# AI_SPEAKER.net
KiCad netlist of a schematic drawn in EAGLE
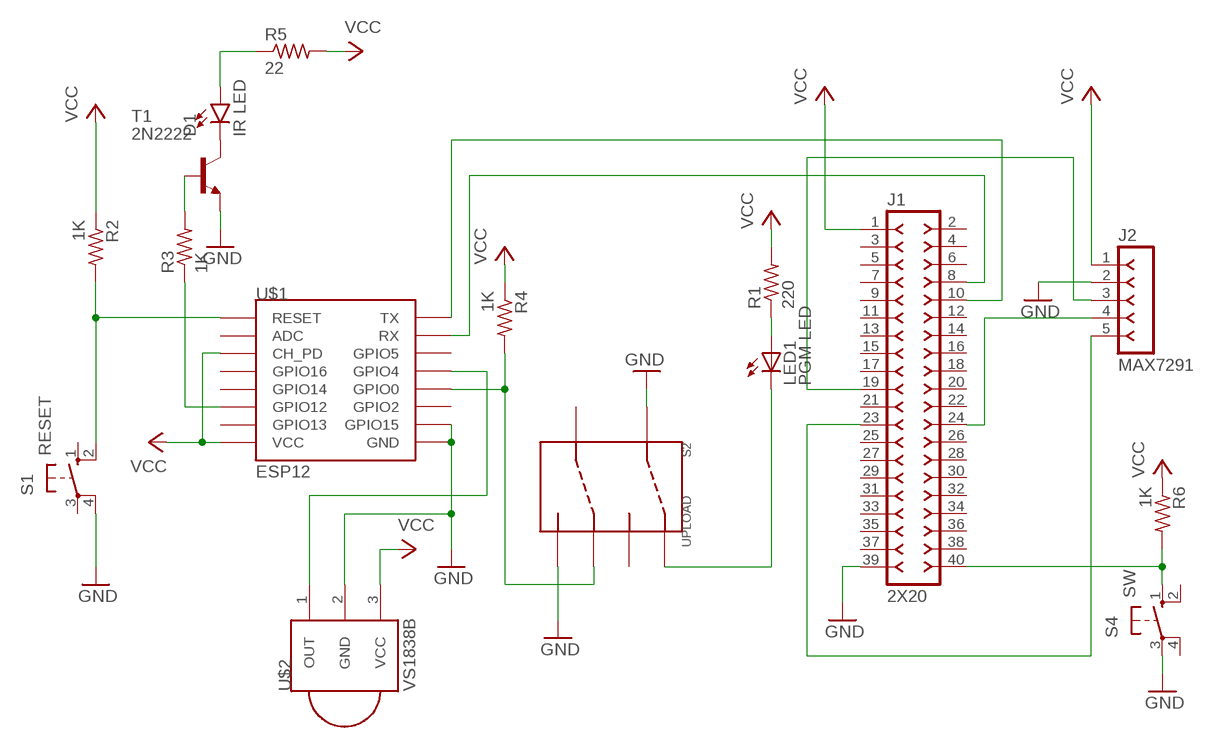
[diagram p0: schematic, sheet 1]

(export (version "E")
  (design (tool "Eeschema 10.0.6"))
  (components
    (comp (ref "D1")
      (value "IR LED")
      (footprint "eagle-import:LED_5MM")
      (fields (field (name "SPICEPREFIX") "D"))
      (libsource (lib "eagle-import") (part "LED-IRTSAL6100"))
    )
    (comp (ref "J1")
      (value "2X20")
      (footprint "eagle-import:DIL-100-2X20")
      (libsource (lib "eagle-import") (part "F-2X20-DIL-100"))
    )
    (comp (ref "J2")
      (value "MAX7291")
      (footprint "eagle-import:SIP-100-05-40")
      (libsource (lib "eagle-import") (part "F-1X05-SIP-100-40"))
    )
    (comp (ref "LED1")
      (value "PGM LED")
      (footprint "eagle-import:LED3MM")
      (libsource (lib "eagle-import") (part "LED3MM"))
    )
    (comp (ref "R1")
      (value "220")
      (footprint "eagle-import:0207_10")
      (libsource (lib "eagle-import") (part "R-US_0207/10"))
    )
    (comp (ref "R2")
      (value "1K")
      (footprint "eagle-import:0207_10")
      (libsource (lib "eagle-import") (part "R-US_0207/10"))
    )
    (comp (ref "R3")
      (value "1K")
      (footprint "eagle-import:0207_10")
      (libsource (lib "eagle-import") (part "R-US_0207/10"))
    )
    (comp (ref "R4")
      (value "1K")
      (footprint "eagle-import:0207_10")
      (libsource (lib "eagle-import") (part "R-US_0207/10"))
    )
    (comp (ref "R5")
      (value "22")
      (footprint "eagle-import:0207_10")
      (libsource (lib "eagle-import") (part "R-US_0207/10"))
    )
    (comp (ref "R6")
      (value "1K")
      (footprint "eagle-import:0207_10")
      (libsource (lib "eagle-import") (part "R-US_0207/10"))
    )
    (comp (ref "S1")
      (value "RESET")
      (footprint "eagle-import:B3F-10XX")
      (fields (field (name "MPN") "B3F-1000"))
      (libsource (lib "eagle-import") (part "10-XX"))
    )
    (comp (ref "S2")
      (value "UPLOAD")
      (footprint "eagle-import:SWITCH-6PIN-LOCK-2.54MM")
      (libsource (lib "eagle-import") (part "SWITCH-6PIN-LOCK-2.54MM"))
    )
    (comp (ref "S4")
      (value "SW")
      (footprint "eagle-import:B3F-10XX")
      (fields (field (name "MPN") "B3F-1000"))
      (libsource (lib "eagle-import") (part "10-XX"))
    )
    (comp (ref "T1")
      (value "2N2222")
      (footprint "eagle-import:TO92-EBC")
      (libsource (lib "eagle-import") (part "-NPN-TO92-EBC2N2222"))
    )
    (comp (ref "U$1")
      (value "ESP12")
      (footprint "eagle-import:ESP12")
      (libsource (lib "eagle-import") (part "ESP12"))
    )
    (comp (ref "U$2")
      (value "VS1838B")
      (footprint "eagle-import:PNA460XM")
      (libsource (lib "eagle-import") (part "PNA460XM"))
    )
  )
  (nets
    (net (code "1") (name "GND") (class "Default")
      (node (ref "J1") (pin "39") (pinfunction "39_39") (pintype "passive"))
      (node (ref "J2") (pin "2") (pinfunction "2_2") (pintype "passive"))
      (node (ref "S1") (pin "4") (pinfunction "P1_4") (pintype "passive"))
      (node (ref "S2") (pin "P$1") (pinfunction "P$1_P$1") (pintype "bidirectional"))
      (node (ref "S2") (pin "P$6") (pinfunction "P$6_P$6") (pintype "bidirectional"))
      (node (ref "S4") (pin "3") (pinfunction "P_3") (pintype "passive"))
      (node (ref "T1") (pin "E") (pinfunction "E_E") (pintype "passive"))
      (node (ref "U$1") (pin "GND") (pinfunction "GND_GND") (pintype "bidirectional"))
      (node (ref "U$1") (pin "GPIO15") (pinfunction "GPIO15_GPIO15") (pintype "bidirectional"))
      (node (ref "U$2") (pin "2") (pinfunction "GND_2") (pintype "power_in"))
    )
    (net (code "2") (name "Net-(D1-C)") (class "Default")
      (node (ref "D1") (pin "K") (pinfunction "C_K") (pintype "passive"))
      (node (ref "T1") (pin "C") (pinfunction "C_C") (pintype "passive"))
    )
    (net (code "3") (name "Net-(D1-PadA)") (class "Default")
      (node (ref "D1") (pin "A") (pinfunction "A_A") (pintype "passive"))
      (node (ref "R5") (pin "1") (pinfunction "1_1") (pintype "passive"))
    )
    (net (code "4") (name "Net-(J1-Pad8)") (class "Default")
      (node (ref "J1") (pin "8") (pinfunction "8_8") (pintype "passive"))
      (node (ref "U$1") (pin "RX") (pinfunction "RX_RX") (pintype "bidirectional"))
    )
    (net (code "5") (name "Net-(J1-Pad10)") (class "Default")
      (node (ref "J1") (pin "10") (pinfunction "10_10") (pintype "passive"))
      (node (ref "U$1") (pin "TX") (pinfunction "TX_TX") (pintype "bidirectional"))
    )
    (net (code "6") (name "Net-(J1-Pad19)") (class "Default")
      (node (ref "J1") (pin "19") (pinfunction "19_19") (pintype "passive"))
      (node (ref "J2") (pin "3") (pinfunction "3_3") (pintype "passive"))
    )
    (net (code "7") (name "Net-(J1-Pad23)") (class "Default")
      (node (ref "J1") (pin "23") (pinfunction "23_23") (pintype "passive"))
      (node (ref "J2") (pin "5") (pinfunction "5_5") (pintype "passive"))
    )
    (net (code "8") (name "Net-(J1-Pad24)") (class "Default")
      (node (ref "J1") (pin "24") (pinfunction "24_24") (pintype "passive"))
      (node (ref "J2") (pin "4") (pinfunction "4_4") (pintype "passive"))
    )
    (net (code "9") (name "Net-(LED1-C)") (class "Default")
      (node (ref "LED1") (pin "K") (pinfunction "C_K") (pintype "passive"))
      (node (ref "S2") (pin "P$2") (pinfunction "P$2_P$2") (pintype "bidirectional"))
    )
    (net (code "10") (name "Net-(LED1-PadA)") (class "Default")
      (node (ref "LED1") (pin "A") (pinfunction "A_A") (pintype "passive"))
      (node (ref "R1") (pin "1") (pinfunction "1_1") (pintype "passive"))
    )
    (net (code "11") (name "Net-(R3-Pad1)") (class "Default")
      (node (ref "R3") (pin "1") (pinfunction "1_1") (pintype "passive"))
      (node (ref "U$1") (pin "GPIO12") (pinfunction "GPIO12_GPIO12") (pintype "bidirectional"))
    )
    (net (code "12") (name "Net-(R3-Pad2)") (class "Default")
      (node (ref "R3") (pin "2") (pinfunction "2_2") (pintype "passive"))
      (node (ref "T1") (pin "B") (pinfunction "B_B") (pintype "passive"))
    )
    (net (code "13") (name "Net-(R4-Pad2)") (class "Default")
      (node (ref "R4") (pin "2") (pinfunction "2_2") (pintype "passive"))
      (node (ref "S2") (pin "P$5") (pinfunction "P$5_P$5") (pintype "bidirectional"))
      (node (ref "U$1") (pin "GPIO0") (pinfunction "GPIO0_GPIO0") (pintype "bidirectional"))
    )
    (net (code "14") (name "Net-(S1-S1)") (class "Default")
      (node (ref "R2") (pin "2") (pinfunction "2_2") (pintype "passive"))
      (node (ref "S1") (pin "2") (pinfunction "S1_2") (pintype "passive"))
      (node (ref "U$1") (pin "RESET") (pinfunction "RESET_RESET") (pintype "bidirectional"))
    )
    (net (code "15") (name "Net-(S4-S)") (class "Default")
      (node (ref "J1") (pin "40") (pinfunction "40_40") (pintype "passive"))
      (node (ref "R6") (pin "2") (pinfunction "2_2") (pintype "passive"))
      (node (ref "S4") (pin "1") (pinfunction "S_1") (pintype "passive"))
    )
    (net (code "16") (name "Net-(U$1-GPIO4)") (class "Default")
      (node (ref "U$1") (pin "GPIO5") (pinfunction "GPIO4_GPIO5") (pintype "bidirectional"))
      (node (ref "U$2") (pin "1") (pinfunction "OUT_1") (pintype "output"))
    )
    (net (code "17") (name "VCC") (class "Default")
      (node (ref "J1") (pin "1") (pinfunction "1_1") (pintype "passive"))
      (node (ref "J2") (pin "1") (pinfunction "1_1") (pintype "passive"))
      (node (ref "R1") (pin "2") (pinfunction "2_2") (pintype "passive"))
      (node (ref "R2") (pin "1") (pinfunction "1_1") (pintype "passive"))
      (node (ref "R4") (pin "1") (pinfunction "1_1") (pintype "passive"))
      (node (ref "R5") (pin "2") (pinfunction "2_2") (pintype "passive"))
      (node (ref "R6") (pin "1") (pinfunction "1_1") (pintype "passive"))
      (node (ref "U$1") (pin "CH_PD") (pinfunction "CH_PD_CH_PD") (pintype "bidirectional"))
      (node (ref "U$1") (pin "VCC") (pinfunction "VCC_VCC") (pintype "bidirectional"))
      (node (ref "U$2") (pin "3") (pinfunction "VCC_3") (pintype "power_in"))
    )
    (net (code "18") (name "unconnected-(J1-Pad2)") (class "Default")
      (node (ref "J1") (pin "2") (pinfunction "2_2") (pintype "passive"))
    )
    (net (code "19") (name "unconnected-(J1-Pad3)") (class "Default")
      (node (ref "J1") (pin "3") (pinfunction "3_3") (pintype "passive"))
    )
    (net (code "20") (name "unconnected-(J1-Pad4)") (class "Default")
      (node (ref "J1") (pin "4") (pinfunction "4_4") (pintype "passive"))
    )
    (net (code "21") (name "unconnected-(J1-Pad5)") (class "Default")
      (node (ref "J1") (pin "5") (pinfunction "5_5") (pintype "passive"))
    )
    (net (code "22") (name "unconnected-(J1-Pad6)") (class "Default")
      (node (ref "J1") (pin "6") (pinfunction "6_6") (pintype "passive"))
    )
    (net (code "23") (name "unconnected-(J1-Pad7)") (class "Default")
      (node (ref "J1") (pin "7") (pinfunction "7_7") (pintype "passive"))
    )
    (net (code "24") (name "unconnected-(J1-Pad9)") (class "Default")
      (node (ref "J1") (pin "9") (pinfunction "9_9") (pintype "passive"))
    )
    (net (code "25") (name "unconnected-(J1-Pad11)") (class "Default")
      (node (ref "J1") (pin "11") (pinfunction "11_11") (pintype "passive"))
    )
    (net (code "26") (name "unconnected-(J1-Pad12)") (class "Default")
      (node (ref "J1") (pin "12") (pinfunction "12_12") (pintype "passive"))
    )
    (net (code "27") (name "unconnected-(J1-Pad13)") (class "Default")
      (node (ref "J1") (pin "13") (pinfunction "13_13") (pintype "passive"))
    )
    (net (code "28") (name "unconnected-(J1-Pad14)") (class "Default")
      (node (ref "J1") (pin "14") (pinfunction "14_14") (pintype "passive"))
    )
    (net (code "29") (name "unconnected-(J1-Pad15)") (class "Default")
      (node (ref "J1") (pin "15") (pinfunction "15_15") (pintype "passive"))
    )
    (net (code "30") (name "unconnected-(J1-Pad16)") (class "Default")
      (node (ref "J1") (pin "16") (pinfunction "16_16") (pintype "passive"))
    )
    (net (code "31") (name "unconnected-(J1-Pad17)") (class "Default")
      (node (ref "J1") (pin "17") (pinfunction "17_17") (pintype "passive"))
    )
    (net (code "32") (name "unconnected-(J1-Pad18)") (class "Default")
      (node (ref "J1") (pin "18") (pinfunction "18_18") (pintype "passive"))
    )
    (net (code "33") (name "unconnected-(J1-Pad20)") (class "Default")
      (node (ref "J1") (pin "20") (pinfunction "20_20") (pintype "passive"))
    )
    (net (code "34") (name "unconnected-(J1-Pad21)") (class "Default")
      (node (ref "J1") (pin "21") (pinfunction "21_21") (pintype "passive"))
    )
    (net (code "35") (name "unconnected-(J1-Pad22)") (class "Default")
      (node (ref "J1") (pin "22") (pinfunction "22_22") (pintype "passive"))
    )
    (net (code "36") (name "unconnected-(J1-Pad25)") (class "Default")
      (node (ref "J1") (pin "25") (pinfunction "25_25") (pintype "passive"))
    )
    (net (code "37") (name "unconnected-(J1-Pad26)") (class "Default")
      (node (ref "J1") (pin "26") (pinfunction "26_26") (pintype "passive"))
    )
    (net (code "38") (name "unconnected-(J1-Pad27)") (class "Default")
      (node (ref "J1") (pin "27") (pinfunction "27_27") (pintype "passive"))
    )
    (net (code "39") (name "unconnected-(J1-Pad28)") (class "Default")
      (node (ref "J1") (pin "28") (pinfunction "28_28") (pintype "passive"))
    )
    (net (code "40") (name "unconnected-(J1-Pad29)") (class "Default")
      (node (ref "J1") (pin "29") (pinfunction "29_29") (pintype "passive"))
    )
    (net (code "41") (name "unconnected-(J1-Pad30)") (class "Default")
      (node (ref "J1") (pin "30") (pinfunction "30_30") (pintype "passive"))
    )
    (net (code "42") (name "unconnected-(J1-Pad31)") (class "Default")
      (node (ref "J1") (pin "31") (pinfunction "31_31") (pintype "passive"))
    )
    (net (code "43") (name "unconnected-(J1-Pad32)") (class "Default")
      (node (ref "J1") (pin "32") (pinfunction "32_32") (pintype "passive"))
    )
    (net (code "44") (name "unconnected-(J1-Pad33)") (class "Default")
      (node (ref "J1") (pin "33") (pinfunction "33_33") (pintype "passive"))
    )
    (net (code "45") (name "unconnected-(J1-Pad34)") (class "Default")
      (node (ref "J1") (pin "34") (pinfunction "34_34") (pintype "passive"))
    )
    (net (code "46") (name "unconnected-(J1-Pad35)") (class "Default")
      (node (ref "J1") (pin "35") (pinfunction "35_35") (pintype "passive"))
    )
    (net (code "47") (name "unconnected-(J1-Pad36)") (class "Default")
      (node (ref "J1") (pin "36") (pinfunction "36_36") (pintype "passive"))
    )
    (net (code "48") (name "unconnected-(J1-Pad37)") (class "Default")
      (node (ref "J1") (pin "37") (pinfunction "37_37") (pintype "passive"))
    )
    (net (code "49") (name "unconnected-(J1-Pad38)") (class "Default")
      (node (ref "J1") (pin "38") (pinfunction "38_38") (pintype "passive"))
    )
    (net (code "50") (name "unconnected-(S1-P-Pad3)") (class "Default")
      (node (ref "S1") (pin "3") (pinfunction "P_3") (pintype "passive"))
    )
    (net (code "51") (name "unconnected-(S1-S-Pad1)") (class "Default")
      (node (ref "S1") (pin "1") (pinfunction "S_1") (pintype "passive"))
    )
    (net (code "52") (name "unconnected-(S2-PadP$3)") (class "Default")
      (node (ref "S2") (pin "P$3") (pinfunction "P$3_P$3") (pintype "bidirectional"))
    )
    (net (code "53") (name "unconnected-(S2-PadP$4)") (class "Default")
      (node (ref "S2") (pin "P$4") (pinfunction "P$4_P$4") (pintype "bidirectional"))
    )
    (net (code "54") (name "unconnected-(S4-P1-Pad4)") (class "Default")
      (node (ref "S4") (pin "4") (pinfunction "P1_4") (pintype "passive"))
    )
    (net (code "55") (name "unconnected-(S4-S1-Pad2)") (class "Default")
      (node (ref "S4") (pin "2") (pinfunction "S1_2") (pintype "passive"))
    )
    (net (code "56") (name "unconnected-(U$1-GPIO5-PadGPIO4)") (class "Default")
      (node (ref "U$1") (pin "GPIO4") (pinfunction "GPIO5_GPIO4") (pintype "bidirectional"))
    )
    (net (code "57") (name "unconnected-(U$1-PadADC)") (class "Default")
      (node (ref "U$1") (pin "ADC") (pinfunction "ADC_ADC") (pintype "bidirectional"))
    )
    (net (code "58") (name "unconnected-(U$1-PadGPIO2)") (class "Default")
      (node (ref "U$1") (pin "GPIO2") (pinfunction "GPIO2_GPIO2") (pintype "bidirectional"))
    )
    (net (code "59") (name "unconnected-(U$1-PadGPIO13)") (class "Default")
      (node (ref "U$1") (pin "GPIO13") (pinfunction "GPIO13_GPIO13") (pintype "bidirectional"))
    )
    (net (code "60") (name "unconnected-(U$1-PadGPIO14)") (class "Default")
      (node (ref "U$1") (pin "GPIO14") (pinfunction "GPIO14_GPIO14") (pintype "bidirectional"))
    )
    (net (code "61") (name "unconnected-(U$1-PadGPIO16)") (class "Default")
      (node (ref "U$1") (pin "GPIO16") (pinfunction "GPIO16_GPIO16") (pintype "bidirectional"))
    )
  )
)
